# eggbothat.net
KiCad netlist of a schematic drawn in EAGLE
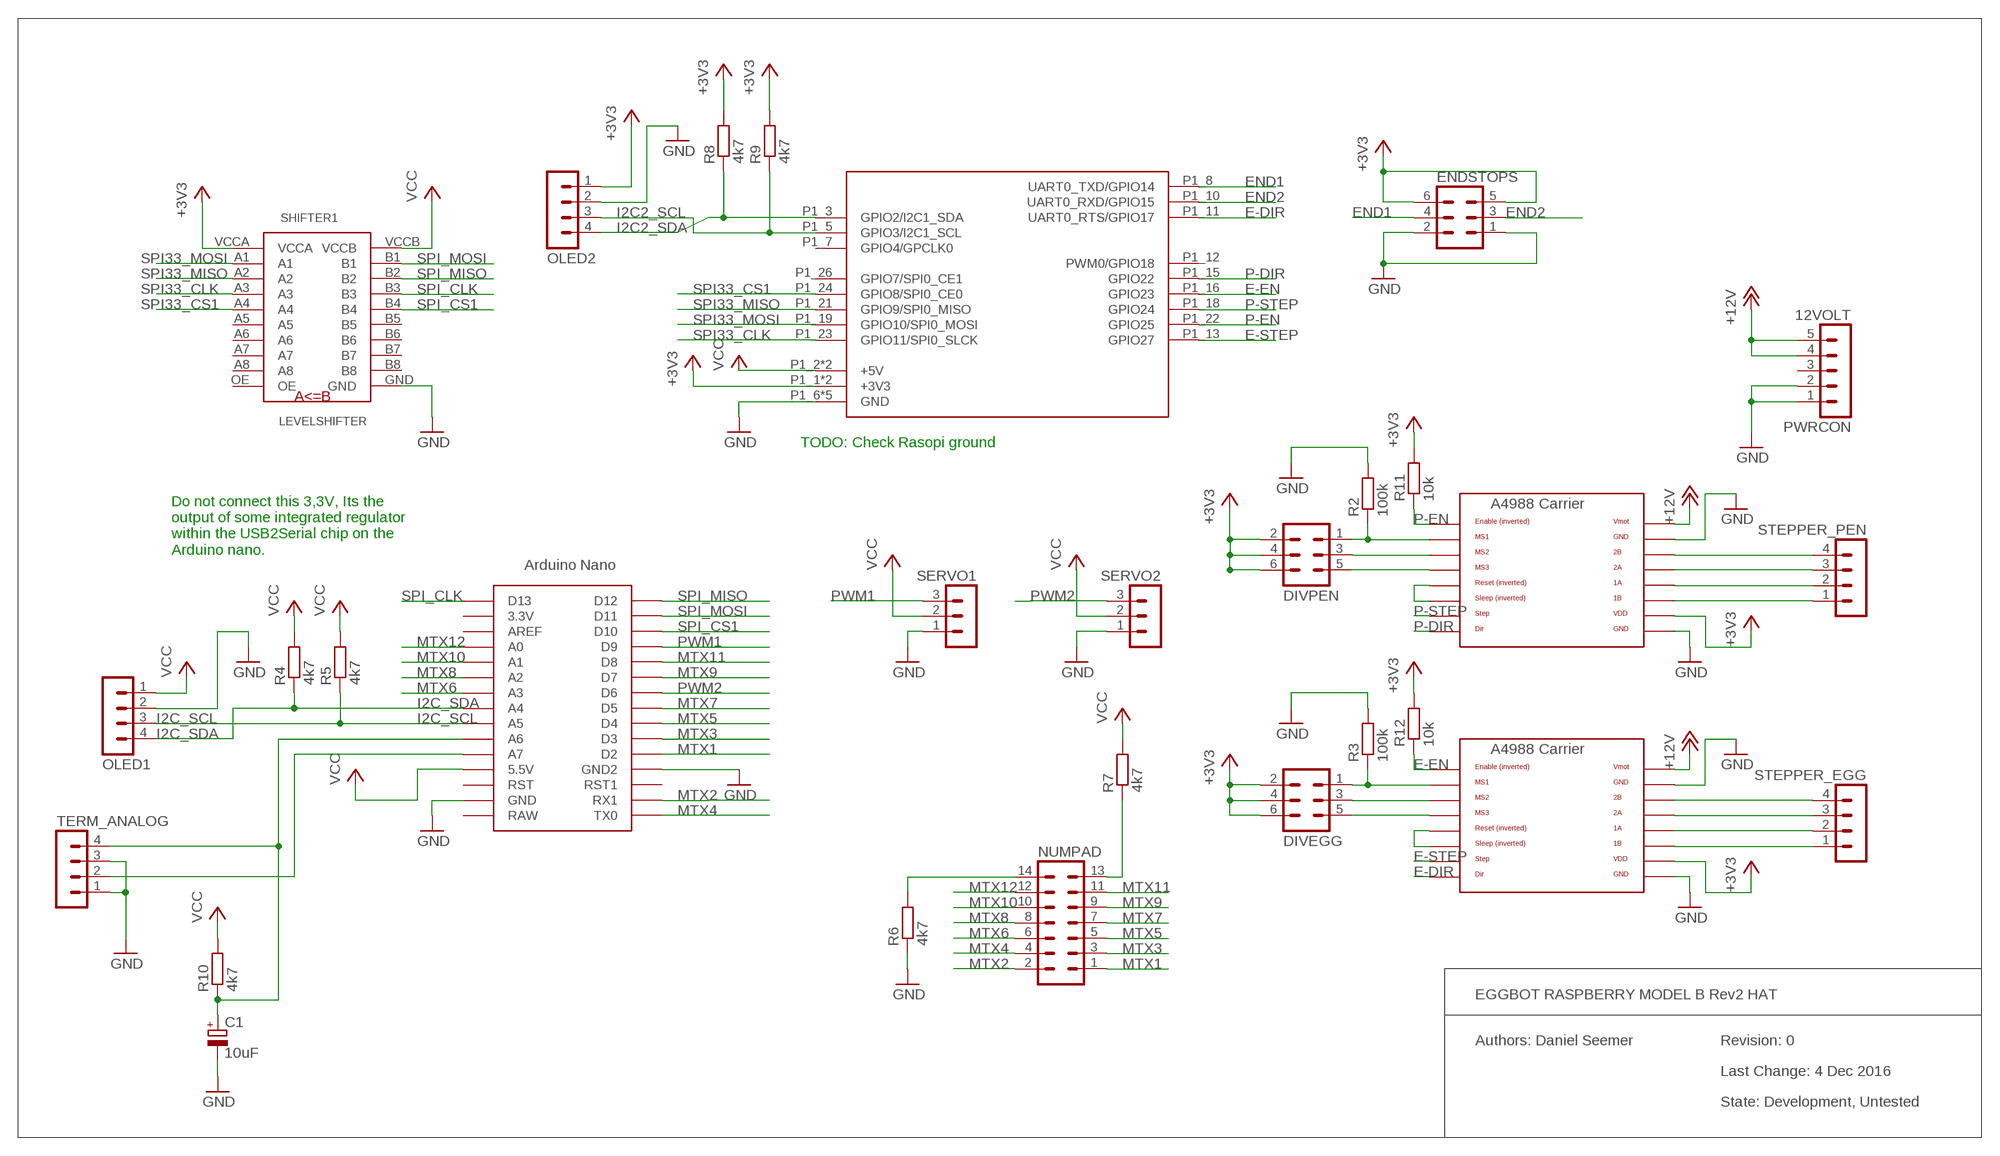
[diagram p0: schematic, sheet 1]

(export (version "E")
  (design (tool "Eeschema 10.0.6"))
  (components
    (comp (ref "12VOLT")
      (value "PWRCON")
      (footprint "eagle-import:MA05-1")
      (libsource (lib "eagle-import") (part "MA05-1"))
    )
    (comp (ref "C1")
      (value "10uF")
      (footprint "eagle-import:E2,5-5")
      (libsource (lib "eagle-import") (part "CPOL-EUE2.5-5"))
    )
    (comp (ref "DIVEGG")
      (value "MA03-2")
      (footprint "eagle-import:MA03-2")
      (libsource (lib "eagle-import") (part "MA03-2"))
    )
    (comp (ref "DIVPEN")
      (value "MA03-2")
      (footprint "eagle-import:MA03-2")
      (libsource (lib "eagle-import") (part "MA03-2"))
    )
    (comp (ref "ENDSTOPS")
      (value "MA03-2")
      (footprint "eagle-import:MA03-2")
      (libsource (lib "eagle-import") (part "MA03-2"))
    )
    (comp (ref "NUMPAD")
      (value "MA07-2")
      (footprint "eagle-import:MA07-2")
      (libsource (lib "eagle-import") (part "MA07-2"))
    )
    (comp (ref "OLED1")
      (value "MA04-1")
      (footprint "eagle-import:MA04-1")
      (libsource (lib "eagle-import") (part "MA04-1"))
    )
    (comp (ref "OLED2")
      (value "MA04-1")
      (footprint "eagle-import:MA04-1")
      (libsource (lib "eagle-import") (part "MA04-1"))
    )
    (comp (ref "R2")
      (value "100k")
      (footprint "eagle-import:R1206")
      (libsource (lib "eagle-import") (part "R-EU_R1206"))
    )
    (comp (ref "R3")
      (value "100k")
      (footprint "eagle-import:R1206")
      (libsource (lib "eagle-import") (part "R-EU_R1206"))
    )
    (comp (ref "R4")
      (value "4k7")
      (footprint "eagle-import:R1206")
      (libsource (lib "eagle-import") (part "R-EU_R1206"))
    )
    (comp (ref "R5")
      (value "4k7")
      (footprint "eagle-import:R1206")
      (libsource (lib "eagle-import") (part "R-EU_R1206"))
    )
    (comp (ref "R6")
      (value "4k7")
      (footprint "eagle-import:R1206")
      (libsource (lib "eagle-import") (part "R-EU_R1206"))
    )
    (comp (ref "R7")
      (value "4k7")
      (footprint "eagle-import:R1206")
      (libsource (lib "eagle-import") (part "R-EU_R1206"))
    )
    (comp (ref "R8")
      (value "4k7")
      (footprint "eagle-import:R1206")
      (libsource (lib "eagle-import") (part "R-EU_R1206"))
    )
    (comp (ref "R9")
      (value "4k7")
      (footprint "eagle-import:R1206")
      (libsource (lib "eagle-import") (part "R-EU_R1206"))
    )
    (comp (ref "R10")
      (value "4k7")
      (footprint "eagle-import:R1206")
      (libsource (lib "eagle-import") (part "R-EU_R1206"))
    )
    (comp (ref "R11")
      (value "10k")
      (footprint "eagle-import:R1206")
      (libsource (lib "eagle-import") (part "R-EU_R1206"))
    )
    (comp (ref "R12")
      (value "10k")
      (footprint "eagle-import:R1206")
      (libsource (lib "eagle-import") (part "R-EU_R1206"))
    )
    (comp (ref "RASPBERRY")
      (value "RPI-B-V2SHIELD")
      (footprint "eagle-import:RPI-B-V2-SHIELD")
      (libsource (lib "eagle-import") (part "RPI-B-V2SHIELD"))
    )
    (comp (ref "SERVO1")
      (value "MA03-1")
      (footprint "eagle-import:MA03-1")
      (libsource (lib "eagle-import") (part "MA03-1"))
    )
    (comp (ref "SERVO2")
      (value "MA03-1")
      (footprint "eagle-import:MA03-1")
      (libsource (lib "eagle-import") (part "MA03-1"))
    )
    (comp (ref "SHIFTER1")
      (value "LEVELSHIFTER")
      (footprint "eagle-import:PLUG_20_S4")
      (libsource (lib "eagle-import") (part "LEVELSHIFTER"))
    )
    (comp (ref "STEPPER_EGG")
      (value "MA04-1")
      (footprint "eagle-import:MA04-1")
      (libsource (lib "eagle-import") (part "MA04-1"))
    )
    (comp (ref "STEPPER_PEN")
      (value "MA04-1")
      (footprint "eagle-import:MA04-1")
      (libsource (lib "eagle-import") (part "MA04-1"))
    )
    (comp (ref "TERM_ANALOG")
      (value "MA04-1")
      (footprint "eagle-import:MA04-1")
      (libsource (lib "eagle-import") (part "MA04-1"))
    )
    (comp (ref "U$1")
      (value "A4988BREAKOUT")
      (footprint "eagle-import:A4988BREAKOUT")
      (libsource (lib "eagle-import") (part "A4988BREAKOUT"))
    )
    (comp (ref "U$2")
      (value "A4988BREAKOUT")
      (footprint "eagle-import:A4988BREAKOUT")
      (libsource (lib "eagle-import") (part "A4988BREAKOUT"))
    )
    (comp (ref "U$4")
      (value "NANO")
      (footprint "eagle-import:NANO")
      (libsource (lib "eagle-import") (part "NANO"))
    )
  )
  (nets
    (net (code "1") (name "+3V3") (class "Default")
      (node (ref "DIVEGG") (pin "2") (pinfunction "2_2") (pintype "passive"))
      (node (ref "DIVEGG") (pin "4") (pinfunction "4_4") (pintype "passive"))
      (node (ref "DIVEGG") (pin "6") (pinfunction "6_6") (pintype "passive"))
      (node (ref "DIVPEN") (pin "2") (pinfunction "2_2") (pintype "passive"))
      (node (ref "DIVPEN") (pin "4") (pinfunction "4_4") (pintype "passive"))
      (node (ref "DIVPEN") (pin "6") (pinfunction "6_6") (pintype "passive"))
      (node (ref "ENDSTOPS") (pin "5") (pinfunction "5_5") (pintype "passive"))
      (node (ref "ENDSTOPS") (pin "6") (pinfunction "6_6") (pintype "passive"))
      (node (ref "OLED2") (pin "1") (pinfunction "1_1") (pintype "passive"))
      (node (ref "R11") (pin "2") (pinfunction "2_2") (pintype "passive"))
      (node (ref "R12") (pin "2") (pinfunction "2_2") (pintype "passive"))
      (node (ref "R8") (pin "2") (pinfunction "2_2") (pintype "passive"))
      (node (ref "R9") (pin "2") (pinfunction "2_2") (pintype "passive"))
      (node (ref "RASPBERRY") (pin "P1_1") (pinfunction "+3V3_P1_1") (pintype "power_in"))
      (node (ref "RASPBERRY") (pin "P1_17") (pinfunction "+3V3_P1_17") (pintype "power_in"))
      (node (ref "SHIFTER1") (pin "VCCA") (pinfunction "VCCA_VCCA") (pintype "bidirectional"))
      (node (ref "U$1") (pin "VDD") (pinfunction "VDD_VDD") (pintype "power_in"))
      (node (ref "U$2") (pin "VDD") (pinfunction "VDD_VDD") (pintype "power_in"))
    )
    (net (code "2") (name "+12V") (class "Default")
      (node (ref "12VOLT") (pin "4") (pinfunction "4_4") (pintype "passive"))
      (node (ref "12VOLT") (pin "5") (pinfunction "5_5") (pintype "passive"))
      (node (ref "U$1") (pin "VMOT") (pinfunction "VMOT_VMOT") (pintype "power_in"))
      (node (ref "U$2") (pin "VMOT") (pinfunction "VMOT_VMOT") (pintype "power_in"))
    )
    (net (code "3") (name "E-DIR") (class "Default")
      (node (ref "RASPBERRY") (pin "P1_11") (pinfunction "UART0_RTS/GPIO17_P1_11") (pintype "bidirectional"))
      (node (ref "U$2") (pin "DIR") (pinfunction "DIR_DIR") (pintype "input"))
    )
    (net (code "4") (name "E-EN") (class "Default")
      (node (ref "R12") (pin "1") (pinfunction "1_1") (pintype "passive"))
      (node (ref "RASPBERRY") (pin "P1_16") (pinfunction "GPIO23_P1_16") (pintype "bidirectional"))
      (node (ref "U$2") (pin "EN") (pinfunction "EN_EN") (pintype "input"))
    )
    (net (code "5") (name "E-STEP") (class "Default")
      (node (ref "RASPBERRY") (pin "P1_13") (pinfunction "GPIO27_P1_13") (pintype "bidirectional"))
      (node (ref "U$2") (pin "STEP") (pinfunction "STEP_STEP") (pintype "input"))
    )
    (net (code "6") (name "END1") (class "Default")
      (node (ref "ENDSTOPS") (pin "4") (pinfunction "4_4") (pintype "passive"))
      (node (ref "RASPBERRY") (pin "P1_8") (pinfunction "UART0_TXD/GPIO14_P1_8") (pintype "bidirectional"))
    )
    (net (code "7") (name "END2") (class "Default")
      (node (ref "ENDSTOPS") (pin "3") (pinfunction "3_3") (pintype "passive"))
      (node (ref "RASPBERRY") (pin "P1_10") (pinfunction "UART0_RXD/GPIO15_P1_10") (pintype "bidirectional"))
    )
    (net (code "8") (name "GND") (class "Default")
      (node (ref "12VOLT") (pin "1") (pinfunction "1_1") (pintype "passive"))
      (node (ref "12VOLT") (pin "2") (pinfunction "2_2") (pintype "passive"))
      (node (ref "C1") (pin "-") (pinfunction "-_-") (pintype "passive"))
      (node (ref "ENDSTOPS") (pin "1") (pinfunction "1_1") (pintype "passive"))
      (node (ref "ENDSTOPS") (pin "2") (pinfunction "2_2") (pintype "passive"))
      (node (ref "OLED1") (pin "2") (pinfunction "2_2") (pintype "passive"))
      (node (ref "OLED2") (pin "2") (pinfunction "2_2") (pintype "passive"))
      (node (ref "R2") (pin "2") (pinfunction "2_2") (pintype "passive"))
      (node (ref "R3") (pin "2") (pinfunction "2_2") (pintype "passive"))
      (node (ref "R6") (pin "1") (pinfunction "1_1") (pintype "passive"))
      (node (ref "RASPBERRY") (pin "P1_14") (pinfunction "GND_P1_14") (pintype "power_in"))
      (node (ref "RASPBERRY") (pin "P1_20") (pinfunction "GND_P1_20") (pintype "power_in"))
      (node (ref "RASPBERRY") (pin "P1_25") (pinfunction "GND_P1_25") (pintype "power_in"))
      (node (ref "RASPBERRY") (pin "P1_6") (pinfunction "GND_P1_6") (pintype "power_in"))
      (node (ref "RASPBERRY") (pin "P1_9") (pinfunction "GND_P1_9") (pintype "power_in"))
      (node (ref "SERVO1") (pin "1") (pinfunction "1_1") (pintype "passive"))
      (node (ref "SERVO2") (pin "1") (pinfunction "1_1") (pintype "passive"))
      (node (ref "SHIFTER1") (pin "GND") (pinfunction "GND_GND") (pintype "bidirectional"))
      (node (ref "TERM_ANALOG") (pin "1") (pinfunction "1_1") (pintype "passive"))
      (node (ref "TERM_ANALOG") (pin "3") (pinfunction "3_3") (pintype "passive"))
      (node (ref "U$1") (pin "GND") (pinfunction "GND_GND") (pintype "power_in"))
      (node (ref "U$1") (pin "GND@0") (pinfunction "GND_GND@0") (pintype "power_in"))
      (node (ref "U$2") (pin "GND") (pinfunction "GND_GND") (pintype "power_in"))
      (node (ref "U$2") (pin "GND@0") (pinfunction "GND_GND@0") (pintype "power_in"))
      (node (ref "U$4") (pin "GND") (pinfunction "GND_GND") (pintype "bidirectional"))
      (node (ref "U$4") (pin "GND1") (pinfunction "GND2_GND1") (pintype "bidirectional"))
    )
    (net (code "9") (name "I2C2_SCL") (class "Default")
      (node (ref "OLED2") (pin "3") (pinfunction "3_3") (pintype "passive"))
      (node (ref "R9") (pin "1") (pinfunction "1_1") (pintype "passive"))
      (node (ref "RASPBERRY") (pin "P1_5") (pinfunction "GPIO3/I2C1_SCL_P1_5") (pintype "bidirectional"))
    )
    (net (code "10") (name "I2C2_SDA") (class "Default")
      (node (ref "OLED2") (pin "4") (pinfunction "4_4") (pintype "passive"))
      (node (ref "R8") (pin "1") (pinfunction "1_1") (pintype "passive"))
      (node (ref "RASPBERRY") (pin "P1_3") (pinfunction "GPIO2/I2C1_SDA_P1_3") (pintype "bidirectional"))
    )
    (net (code "11") (name "I2C_SCL") (class "Default")
      (node (ref "OLED1") (pin "3") (pinfunction "3_3") (pintype "passive"))
      (node (ref "R5") (pin "1") (pinfunction "1_1") (pintype "passive"))
      (node (ref "U$4") (pin "A5") (pinfunction "A5_A5") (pintype "bidirectional"))
    )
    (net (code "12") (name "I2C_SDA") (class "Default")
      (node (ref "OLED1") (pin "4") (pinfunction "4_4") (pintype "passive"))
      (node (ref "R4") (pin "1") (pinfunction "1_1") (pintype "passive"))
      (node (ref "U$4") (pin "A4") (pinfunction "A4_A4") (pintype "bidirectional"))
    )
    (net (code "13") (name "MTX1") (class "Default")
      (node (ref "NUMPAD") (pin "1") (pinfunction "1_1") (pintype "passive"))
      (node (ref "U$4") (pin "D2") (pinfunction "D2_D2") (pintype "bidirectional"))
    )
    (net (code "14") (name "MTX2") (class "Default")
      (node (ref "NUMPAD") (pin "2") (pinfunction "2_2") (pintype "passive"))
      (node (ref "U$4") (pin "RX1") (pinfunction "RX1_RX1") (pintype "bidirectional"))
    )
    (net (code "15") (name "MTX3") (class "Default")
      (node (ref "NUMPAD") (pin "3") (pinfunction "3_3") (pintype "passive"))
      (node (ref "U$4") (pin "D3") (pinfunction "D3_D3") (pintype "bidirectional"))
    )
    (net (code "16") (name "MTX4") (class "Default")
      (node (ref "NUMPAD") (pin "4") (pinfunction "4_4") (pintype "passive"))
      (node (ref "U$4") (pin "TX0") (pinfunction "TX0_TX0") (pintype "bidirectional"))
    )
    (net (code "17") (name "MTX5") (class "Default")
      (node (ref "NUMPAD") (pin "5") (pinfunction "5_5") (pintype "passive"))
      (node (ref "U$4") (pin "D4") (pinfunction "D4_D4") (pintype "bidirectional"))
    )
    (net (code "18") (name "MTX6") (class "Default")
      (node (ref "NUMPAD") (pin "6") (pinfunction "6_6") (pintype "passive"))
      (node (ref "U$4") (pin "A3") (pinfunction "A3_A3") (pintype "bidirectional"))
    )
    (net (code "19") (name "MTX7") (class "Default")
      (node (ref "NUMPAD") (pin "7") (pinfunction "7_7") (pintype "passive"))
      (node (ref "U$4") (pin "D5") (pinfunction "D5_D5") (pintype "bidirectional"))
    )
    (net (code "20") (name "MTX8") (class "Default")
      (node (ref "NUMPAD") (pin "8") (pinfunction "8_8") (pintype "passive"))
      (node (ref "U$4") (pin "A2") (pinfunction "A2_A2") (pintype "bidirectional"))
    )
    (net (code "21") (name "MTX9") (class "Default")
      (node (ref "NUMPAD") (pin "9") (pinfunction "9_9") (pintype "passive"))
      (node (ref "U$4") (pin "D7") (pinfunction "D7_D7") (pintype "bidirectional"))
    )
    (net (code "22") (name "MTX10") (class "Default")
      (node (ref "NUMPAD") (pin "10") (pinfunction "10_10") (pintype "passive"))
      (node (ref "U$4") (pin "A1") (pinfunction "A1_A1") (pintype "bidirectional"))
    )
    (net (code "23") (name "MTX11") (class "Default")
      (node (ref "NUMPAD") (pin "11") (pinfunction "11_11") (pintype "passive"))
      (node (ref "U$4") (pin "D8") (pinfunction "D8_D8") (pintype "bidirectional"))
    )
    (net (code "24") (name "MTX12") (class "Default")
      (node (ref "NUMPAD") (pin "12") (pinfunction "12_12") (pintype "passive"))
      (node (ref "U$4") (pin "A0") (pinfunction "A0_A0") (pintype "bidirectional"))
    )
    (net (code "25") (name "Net-(C1-Pad+)") (class "Default")
      (node (ref "C1") (pin "+") (pinfunction "+_+") (pintype "passive"))
      (node (ref "R10") (pin "1") (pinfunction "1_1") (pintype "passive"))
      (node (ref "TERM_ANALOG") (pin "4") (pinfunction "4_4") (pintype "passive"))
      (node (ref "U$4") (pin "A6") (pinfunction "A6_A6") (pintype "bidirectional"))
    )
    (net (code "26") (name "Net-(DIVEGG-Pad1)") (class "Default")
      (node (ref "DIVEGG") (pin "1") (pinfunction "1_1") (pintype "passive"))
      (node (ref "R3") (pin "1") (pinfunction "1_1") (pintype "passive"))
      (node (ref "U$2") (pin "MS1") (pinfunction "MS1_MS1") (pintype "input"))
    )
    (net (code "27") (name "Net-(DIVEGG-Pad3)") (class "Default")
      (node (ref "DIVEGG") (pin "3") (pinfunction "3_3") (pintype "passive"))
      (node (ref "U$2") (pin "MS2") (pinfunction "MS2_MS2") (pintype "input"))
    )
    (net (code "28") (name "Net-(DIVEGG-Pad5)") (class "Default")
      (node (ref "DIVEGG") (pin "5") (pinfunction "5_5") (pintype "passive"))
      (node (ref "U$2") (pin "MS3") (pinfunction "MS3_MS3") (pintype "input"))
    )
    (net (code "29") (name "Net-(DIVPEN-Pad1)") (class "Default")
      (node (ref "DIVPEN") (pin "1") (pinfunction "1_1") (pintype "passive"))
      (node (ref "R2") (pin "1") (pinfunction "1_1") (pintype "passive"))
      (node (ref "U$1") (pin "MS1") (pinfunction "MS1_MS1") (pintype "input"))
    )
    (net (code "30") (name "Net-(DIVPEN-Pad3)") (class "Default")
      (node (ref "DIVPEN") (pin "3") (pinfunction "3_3") (pintype "passive"))
      (node (ref "U$1") (pin "MS2") (pinfunction "MS2_MS2") (pintype "input"))
    )
    (net (code "31") (name "Net-(DIVPEN-Pad5)") (class "Default")
      (node (ref "DIVPEN") (pin "5") (pinfunction "5_5") (pintype "passive"))
      (node (ref "U$1") (pin "MS3") (pinfunction "MS3_MS3") (pintype "input"))
    )
    (net (code "32") (name "Net-(NUMPAD-Pad13)") (class "Default")
      (node (ref "NUMPAD") (pin "13") (pinfunction "13_13") (pintype "passive"))
      (node (ref "R7") (pin "1") (pinfunction "1_1") (pintype "passive"))
    )
    (net (code "33") (name "Net-(NUMPAD-Pad14)") (class "Default")
      (node (ref "NUMPAD") (pin "14") (pinfunction "14_14") (pintype "passive"))
      (node (ref "R6") (pin "2") (pinfunction "2_2") (pintype "passive"))
    )
    (net (code "34") (name "Net-(STEPPER_EGG-Pad1)") (class "Default")
      (node (ref "STEPPER_EGG") (pin "1") (pinfunction "1_1") (pintype "passive"))
      (node (ref "U$2") (pin "1B") (pinfunction "1B_1B") (pintype "output"))
    )
    (net (code "35") (name "Net-(STEPPER_EGG-Pad2)") (class "Default")
      (node (ref "STEPPER_EGG") (pin "2") (pinfunction "2_2") (pintype "passive"))
      (node (ref "U$2") (pin "1A") (pinfunction "1A_1A") (pintype "output"))
    )
    (net (code "36") (name "Net-(STEPPER_EGG-Pad3)") (class "Default")
      (node (ref "STEPPER_EGG") (pin "3") (pinfunction "3_3") (pintype "passive"))
      (node (ref "U$2") (pin "2A") (pinfunction "2A_2A") (pintype "output"))
    )
    (net (code "37") (name "Net-(STEPPER_EGG-Pad4)") (class "Default")
      (node (ref "STEPPER_EGG") (pin "4") (pinfunction "4_4") (pintype "passive"))
      (node (ref "U$2") (pin "2B") (pinfunction "2B_2B") (pintype "output"))
    )
    (net (code "38") (name "Net-(STEPPER_PEN-Pad1)") (class "Default")
      (node (ref "STEPPER_PEN") (pin "1") (pinfunction "1_1") (pintype "passive"))
      (node (ref "U$1") (pin "1B") (pinfunction "1B_1B") (pintype "output"))
    )
    (net (code "39") (name "Net-(STEPPER_PEN-Pad2)") (class "Default")
      (node (ref "STEPPER_PEN") (pin "2") (pinfunction "2_2") (pintype "passive"))
      (node (ref "U$1") (pin "1A") (pinfunction "1A_1A") (pintype "output"))
    )
    (net (code "40") (name "Net-(STEPPER_PEN-Pad3)") (class "Default")
      (node (ref "STEPPER_PEN") (pin "3") (pinfunction "3_3") (pintype "passive"))
      (node (ref "U$1") (pin "2A") (pinfunction "2A_2A") (pintype "output"))
    )
    (net (code "41") (name "Net-(STEPPER_PEN-Pad4)") (class "Default")
      (node (ref "STEPPER_PEN") (pin "4") (pinfunction "4_4") (pintype "passive"))
      (node (ref "U$1") (pin "2B") (pinfunction "2B_2B") (pintype "output"))
    )
    (net (code "42") (name "Net-(TERM_ANALOG-Pad2)") (class "Default")
      (node (ref "TERM_ANALOG") (pin "2") (pinfunction "2_2") (pintype "passive"))
      (node (ref "U$4") (pin "A7") (pinfunction "A7_A7") (pintype "bidirectional"))
    )
    (net (code "43") (name "Net-(U$1-SLEEP)") (class "Default")
      (node (ref "U$1") (pin "RST") (pinfunction "RST_RST") (pintype "input"))
      (node (ref "U$1") (pin "SLP") (pinfunction "SLEEP_SLP") (pintype "input"))
    )
    (net (code "44") (name "Net-(U$2-SLEEP)") (class "Default")
      (node (ref "U$2") (pin "RST") (pinfunction "RST_RST") (pintype "input"))
      (node (ref "U$2") (pin "SLP") (pinfunction "SLEEP_SLP") (pintype "input"))
    )
    (net (code "45") (name "P-DIR") (class "Default")
      (node (ref "RASPBERRY") (pin "P1_15") (pinfunction "GPIO22_P1_15") (pintype "bidirectional"))
      (node (ref "U$1") (pin "DIR") (pinfunction "DIR_DIR") (pintype "input"))
    )
    (net (code "46") (name "P-EN") (class "Default")
      (node (ref "R11") (pin "1") (pinfunction "1_1") (pintype "passive"))
      (node (ref "RASPBERRY") (pin "P1_22") (pinfunction "GPIO25_P1_22") (pintype "bidirectional"))
      (node (ref "U$1") (pin "EN") (pinfunction "EN_EN") (pintype "input"))
    )
    (net (code "47") (name "P-STEP") (class "Default")
      (node (ref "RASPBERRY") (pin "P1_18") (pinfunction "GPIO24_P1_18") (pintype "bidirectional"))
      (node (ref "U$1") (pin "STEP") (pinfunction "STEP_STEP") (pintype "input"))
    )
    (net (code "48") (name "PWM1") (class "Default")
      (node (ref "SERVO1") (pin "3") (pinfunction "3_3") (pintype "passive"))
      (node (ref "U$4") (pin "D9") (pinfunction "D9_D9") (pintype "bidirectional"))
    )
    (net (code "49") (name "PWM2") (class "Default")
      (node (ref "SERVO2") (pin "3") (pinfunction "3_3") (pintype "passive"))
      (node (ref "U$4") (pin "D6") (pinfunction "D6_D6") (pintype "bidirectional"))
    )
    (net (code "50") (name "SPI33_CLK") (class "Default")
      (node (ref "RASPBERRY") (pin "P1_23") (pinfunction "GPIO11/SPI0_SLCK_P1_23") (pintype "bidirectional"))
      (node (ref "SHIFTER1") (pin "A3") (pinfunction "A3_A3") (pintype "bidirectional"))
    )
    (net (code "51") (name "SPI33_CS1") (class "Default")
      (node (ref "RASPBERRY") (pin "P1_24") (pinfunction "GPIO8/SPI0_CE0_P1_24") (pintype "bidirectional"))
      (node (ref "SHIFTER1") (pin "A4") (pinfunction "A4_A4") (pintype "bidirectional"))
    )
    (net (code "52") (name "SPI33_MISO") (class "Default")
      (node (ref "RASPBERRY") (pin "P1_21") (pinfunction "GPIO9/SPI0_MISO_P1_21") (pintype "bidirectional"))
      (node (ref "SHIFTER1") (pin "A2") (pinfunction "A2_A2") (pintype "bidirectional"))
    )
    (net (code "53") (name "SPI33_MOSI") (class "Default")
      (node (ref "RASPBERRY") (pin "P1_19") (pinfunction "GPIO10/SPI0_MOSI_P1_19") (pintype "bidirectional"))
      (node (ref "SHIFTER1") (pin "A1") (pinfunction "A1_A1") (pintype "bidirectional"))
    )
    (net (code "54") (name "SPI_CLK") (class "Default")
      (node (ref "SHIFTER1") (pin "B3") (pinfunction "B3_B3") (pintype "bidirectional"))
      (node (ref "U$4") (pin "D13") (pinfunction "D13_D13") (pintype "bidirectional"))
    )
    (net (code "55") (name "SPI_CS1") (class "Default")
      (node (ref "SHIFTER1") (pin "B4") (pinfunction "B4_B4") (pintype "bidirectional"))
      (node (ref "U$4") (pin "D10") (pinfunction "D10_D10") (pintype "bidirectional"))
    )
    (net (code "56") (name "SPI_MISO") (class "Default")
      (node (ref "SHIFTER1") (pin "B2") (pinfunction "B2_B2") (pintype "bidirectional"))
      (node (ref "U$4") (pin "D12") (pinfunction "D12_D12") (pintype "bidirectional"))
    )
    (net (code "57") (name "SPI_MOSI") (class "Default")
      (node (ref "SHIFTER1") (pin "B1") (pinfunction "B1_B1") (pintype "bidirectional"))
      (node (ref "U$4") (pin "D11") (pinfunction "D11_D11") (pintype "bidirectional"))
    )
    (net (code "58") (name "VCC") (class "Default")
      (node (ref "OLED1") (pin "1") (pinfunction "1_1") (pintype "passive"))
      (node (ref "R10") (pin "2") (pinfunction "2_2") (pintype "passive"))
      (node (ref "R4") (pin "2") (pinfunction "2_2") (pintype "passive"))
      (node (ref "R5") (pin "2") (pinfunction "2_2") (pintype "passive"))
      (node (ref "R7") (pin "2") (pinfunction "2_2") (pintype "passive"))
      (node (ref "RASPBERRY") (pin "P1_2") (pinfunction "+5V_P1_2") (pintype "power_in"))
      (node (ref "RASPBERRY") (pin "P1_4") (pinfunction "+5V_P1_4") (pintype "power_in"))
      (node (ref "SERVO1") (pin "2") (pinfunction "2_2") (pintype "passive"))
      (node (ref "SERVO2") (pin "2") (pinfunction "2_2") (pintype "passive"))
      (node (ref "SHIFTER1") (pin "VCCB") (pinfunction "VCCB_VCCB") (pintype "bidirectional"))
      (node (ref "U$4") (pin "5V") (pinfunction "5.5V_5V") (pintype "bidirectional"))
    )
    (net (code "59") (name "unconnected-(12VOLT-Pad3)") (class "Default")
      (node (ref "12VOLT") (pin "3") (pinfunction "3_3") (pintype "passive"))
    )
    (net (code "60") (name "unconnected-(RASPBERRY-GPIO4{slash}GPCLK0-PadP1_7)") (class "Default")
      (node (ref "RASPBERRY") (pin "P1_7") (pinfunction "GPIO4/GPCLK0_P1_7") (pintype "bidirectional"))
    )
    (net (code "61") (name "unconnected-(RASPBERRY-GPIO7{slash}SPI0_CE1-PadP1_26)") (class "Default")
      (node (ref "RASPBERRY") (pin "P1_26") (pinfunction "GPIO7/SPI0_CE1_P1_26") (pintype "bidirectional"))
    )
    (net (code "62") (name "unconnected-(RASPBERRY-PWM0{slash}GPIO18-PadP1_12)") (class "Default")
      (node (ref "RASPBERRY") (pin "P1_12") (pinfunction "PWM0/GPIO18_P1_12") (pintype "bidirectional"))
    )
    (net (code "63") (name "unconnected-(SHIFTER1-PadA5)") (class "Default")
      (node (ref "SHIFTER1") (pin "A5") (pinfunction "A5_A5") (pintype "bidirectional"))
    )
    (net (code "64") (name "unconnected-(SHIFTER1-PadA6)") (class "Default")
      (node (ref "SHIFTER1") (pin "A6") (pinfunction "A6_A6") (pintype "bidirectional"))
    )
    (net (code "65") (name "unconnected-(SHIFTER1-PadA7)") (class "Default")
      (node (ref "SHIFTER1") (pin "A7") (pinfunction "A7_A7") (pintype "bidirectional"))
    )
    (net (code "66") (name "unconnected-(SHIFTER1-PadA8)") (class "Default")
      (node (ref "SHIFTER1") (pin "A8") (pinfunction "A8_A8") (pintype "bidirectional"))
    )
    (net (code "67") (name "unconnected-(SHIFTER1-PadB5)") (class "Default")
      (node (ref "SHIFTER1") (pin "B5") (pinfunction "B5_B5") (pintype "bidirectional"))
    )
    (net (code "68") (name "unconnected-(SHIFTER1-PadB6)") (class "Default")
      (node (ref "SHIFTER1") (pin "B6") (pinfunction "B6_B6") (pintype "bidirectional"))
    )
    (net (code "69") (name "unconnected-(SHIFTER1-PadB7)") (class "Default")
      (node (ref "SHIFTER1") (pin "B7") (pinfunction "B7_B7") (pintype "bidirectional"))
    )
    (net (code "70") (name "unconnected-(SHIFTER1-PadB8)") (class "Default")
      (node (ref "SHIFTER1") (pin "B8") (pinfunction "B8_B8") (pintype "bidirectional"))
    )
    (net (code "71") (name "unconnected-(SHIFTER1-PadOE)") (class "Default")
      (node (ref "SHIFTER1") (pin "OE") (pinfunction "OE_OE") (pintype "bidirectional"))
    )
    (net (code "72") (name "unconnected-(U$4-Pad3.3V)") (class "Default")
      (node (ref "U$4") (pin "3.3V") (pinfunction "3.3V_3.3V") (pintype "bidirectional"))
    )
    (net (code "73") (name "unconnected-(U$4-PadAREF)") (class "Default")
      (node (ref "U$4") (pin "AREF") (pinfunction "AREF_AREF") (pintype "bidirectional"))
    )
    (net (code "74") (name "unconnected-(U$4-PadRAW)") (class "Default")
      (node (ref "U$4") (pin "RAW") (pinfunction "RAW_RAW") (pintype "bidirectional"))
    )
    (net (code "75") (name "unconnected-(U$4-PadRST)") (class "Default")
      (node (ref "U$4") (pin "RST") (pinfunction "RST_RST") (pintype "bidirectional"))
    )
    (net (code "76") (name "unconnected-(U$4-PadRST1)") (class "Default")
      (node (ref "U$4") (pin "RST1") (pinfunction "RST1_RST1") (pintype "bidirectional"))
    )
  )
)
